# 12_to__3_3.net
KiCad netlist of a schematic drawn in Altium Designer
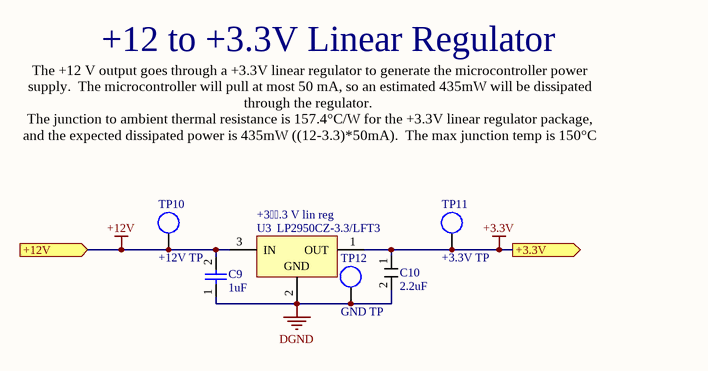
[diagram p0: +12_to_+3.3.SchDoc]

(export (version "E")
  (design (tool "Eeschema 10.0.6"))
  (components
    (comp (ref "C9")
      (value "1uF")
      (footprint "CAPC2113X120X50LL20T30")
      (fields
        (field (name "MANUFACTURER") "AVX Interconnect / Elco")
        (field (name "PART NUMBER") "TAJR105K020RNJ")
      )
      (libsource (lib "Altium Content Vault") (part "CAP"))
    )
    (comp (ref "C10")
      (value "2.2uF")
      (footprint "CAPMP3216X180N")
      (libsource (lib "California Institute of Technology") (part "F931V225KAA-Symbol-1"))
    )
    (comp (ref "TP10")
      (value "+12V TP")
      (footprint "PCBComponent_1")
      (libsource (lib "test-point") (part "Component_1"))
    )
    (comp (ref "TP11")
      (value "+3.3V TP")
      (footprint "PCBComponent_1")
      (libsource (lib "test-point") (part "Component_1"))
    )
    (comp (ref "TP12")
      (value "GND TP")
      (footprint "PCBComponent_1")
      (libsource (lib "test-point") (part "Component_1"))
    )
    (comp (ref "U3")
      (value "LP2950CZ-3.3/LFT3")
      (footprint "LP0003A")
      (description "Series of Adjustable Micropower Voltage Regulators, 3-pin TO-92, Pb-Free")
      (fields (field (name "MANUFACTURER") "Texas Instruments"))
      (libsource (lib "Altium Content Vault") (part "PM-REG-LM78L05-SIL3"))
    )
  )
  (nets
    (net (code "1") (name "+3.3V") (class "Default")
      (node (ref "C10") (pin "1") (pinfunction "-_1") (pintype "passive"))
      (node (ref "TP11") (pin "TP") (pinfunction "TP_TP") (pintype "passive"))
      (node (ref "U3") (pin "1") (pinfunction "OUT_1") (pintype "power_in"))
    )
    (net (code "2") (name "+12V") (class "Default")
      (node (ref "C9") (pin "2") (pinfunction "2_2") (pintype "passive"))
      (node (ref "TP10") (pin "TP") (pinfunction "TP_TP") (pintype "passive"))
      (node (ref "U3") (pin "3") (pinfunction "IN_3") (pintype "power_in"))
    )
    (net (code "3") (name "DGND") (class "Default")
      (node (ref "C10") (pin "2") (pinfunction "-_2") (pintype "passive"))
      (node (ref "C9") (pin "1") (pinfunction "1_1") (pintype "passive"))
      (node (ref "TP12") (pin "TP") (pinfunction "TP_TP") (pintype "passive"))
      (node (ref "U3") (pin "2") (pinfunction "GND_2") (pintype "power_in"))
    )
  )
)
